# PowerSupply.net
KiCad netlist of a schematic drawn in Altium Designer
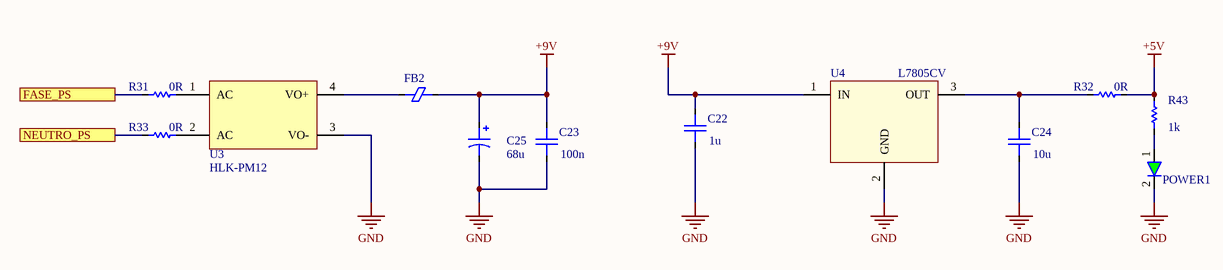
[diagram p0: PowerSupply.SchDoc]

(export (version "E")
  (design (tool "Eeschema 10.0.6"))
  (components
    (comp (ref "C22")
      (value "1u")
      (footprint "CAP0603")
      (description "CAP CER SMD 0603")
      (fields (field (name "Comment") "Capacitor"))
      (libsource (lib "Simbolos") (part "Capacitor"))
    )
    (comp (ref "C23")
      (value "100n")
      (footprint "CAP0603")
      (description "CAP CER SMD 0603")
      (fields (field (name "Comment") "Capacitor"))
      (libsource (lib "Simbolos") (part "Capacitor"))
    )
    (comp (ref "C24")
      (value "10u")
      (footprint "CAP0603")
      (description "CAP CER SMD 0603")
      (fields (field (name "Comment") "Capacitor"))
      (libsource (lib "Simbolos") (part "Capacitor"))
    )
    (comp (ref "C25")
      (value "68u")
      (footprint "CAP_ALU_6.3x7.7")
      (description "Capacitor Polarizado")
      (fields (field (name "Comment") "Capacitor"))
      (libsource (lib "Simbolos") (part "Capacitor Polarizado"))
    )
    (comp (ref "FB2")
      (value "Ferrite Bead")
      (footprint "FB0603")
      (libsource (lib "Simbolos") (part "Ferrite Bead"))
    )
    (comp (ref "POWER1")
      (value "LED Green")
      (footprint "HDR1X2")
      (libsource (lib "Simbolos") (part "LED Green"))
    )
    (comp (ref "R31")
      (value "0R")
      (footprint "RES0603")
      (description "Resistor")
      (libsource (lib "Simbolos") (part "Resistor"))
    )
    (comp (ref "R32")
      (value "0R")
      (footprint "RES0603")
      (description "Resistor")
      (libsource (lib "Simbolos") (part "Resistor"))
    )
    (comp (ref "R33")
      (value "0R")
      (footprint "RES0603")
      (description "Resistor")
      (libsource (lib "Simbolos") (part "Resistor"))
    )
    (comp (ref "R43")
      (value "1k")
      (footprint "RES0603")
      (description "Resistor")
      (libsource (lib "Simbolos") (part "Resistor"))
    )
    (comp (ref "U3")
      (value "HLK-PM12")
      (footprint "HLP-PM12")
      (description "Flyback power supply AC to 12V@3W")
      (fields (field (name "PART NUMBER") "HLK-PM12") (field (name "MANUFACTURER") "HI-LINK"))
      (libsource (lib "Simbolos") (part "HLK-PM12"))
    )
    (comp (ref "U4")
      (value "L7805CV")
      (footprint "TO-220 - 90°")
      (description "IC REG LINEAR 5V 1.5A TO220")
      (fields (field (name "MANUFACTURER") "STMicroelectronics") (field (name "PART NUMBER") "L7805CV"))
      (libsource (lib "Simbolos") (part "L7805CV"))
    )
  )
  (nets
    (net (code "1") (name "+5V") (class "Default")
      (node (ref "R32") (pin "1") (pinfunction "1_1") (pintype "passive"))
      (node (ref "R43") (pin "1") (pinfunction "1_1") (pintype "passive"))
    )
    (net (code "2") (name "+9V") (class "Default")
      (node (ref "C22") (pin "2") (pinfunction "2_2") (pintype "passive"))
      (node (ref "C23") (pin "2") (pinfunction "2_2") (pintype "passive"))
      (node (ref "C25") (pin "1") (pinfunction "1_1") (pintype "passive"))
      (node (ref "FB2") (pin "1") (pinfunction "1_1") (pintype "passive"))
      (node (ref "U4") (pin "1") (pinfunction "IN_1") (pintype "passive"))
    )
    (net (code "3") (name "/FASE_PS") (class "Default")
      (node (ref "R31") (pin "2") (pinfunction "2_2") (pintype "passive"))
    )
    (net (code "4") (name "/NEUTRO_PS") (class "Default")
      (node (ref "R33") (pin "2") (pinfunction "2_2") (pintype "passive"))
    )
    (net (code "5") (name "GND") (class "Default")
      (node (ref "C22") (pin "1") (pinfunction "1_1") (pintype "passive"))
      (node (ref "C23") (pin "1") (pinfunction "1_1") (pintype "passive"))
      (node (ref "C24") (pin "1") (pinfunction "1_1") (pintype "passive"))
      (node (ref "C25") (pin "2") (pinfunction "2_2") (pintype "passive"))
      (node (ref "POWER1") (pin "2") (pinfunction "K_2") (pintype "passive"))
      (node (ref "U3") (pin "3") (pinfunction "VO-_3") (pintype "passive"))
      (node (ref "U4") (pin "2") (pinfunction "GND_2") (pintype "passive"))
    )
    (net (code "6") (name "Net-(POWER1-A)") (class "Default")
      (node (ref "POWER1") (pin "1") (pinfunction "A_1") (pintype "passive"))
      (node (ref "R43") (pin "2") (pinfunction "2_2") (pintype "passive"))
    )
    (net (code "7") (name "Net-(R31-Pad1)") (class "Default")
      (node (ref "R31") (pin "1") (pinfunction "1_1") (pintype "passive"))
      (node (ref "U3") (pin "1") (pinfunction "AC_1") (pintype "passive"))
    )
    (net (code "8") (name "Net-(R33-Pad1)") (class "Default")
      (node (ref "R33") (pin "1") (pinfunction "1_1") (pintype "passive"))
      (node (ref "U3") (pin "2") (pinfunction "AC_2") (pintype "passive"))
    )
    (net (code "9") (name "Net-(U3-VO+)") (class "Default")
      (node (ref "FB2") (pin "2") (pinfunction "2_2") (pintype "passive"))
      (node (ref "U3") (pin "4") (pinfunction "VO+_4") (pintype "passive"))
    )
    (net (code "10") (name "Net-(U4-OUT)") (class "Default")
      (node (ref "C24") (pin "2") (pinfunction "2_2") (pintype "passive"))
      (node (ref "R32") (pin "2") (pinfunction "2_2") (pintype "passive"))
      (node (ref "U4") (pin "3") (pinfunction "OUT_3") (pintype "passive"))
    )
  )
)
